# SCH5_Main_computer_USB2-0.net
KiCad netlist of a schematic drawn in Altium Designer
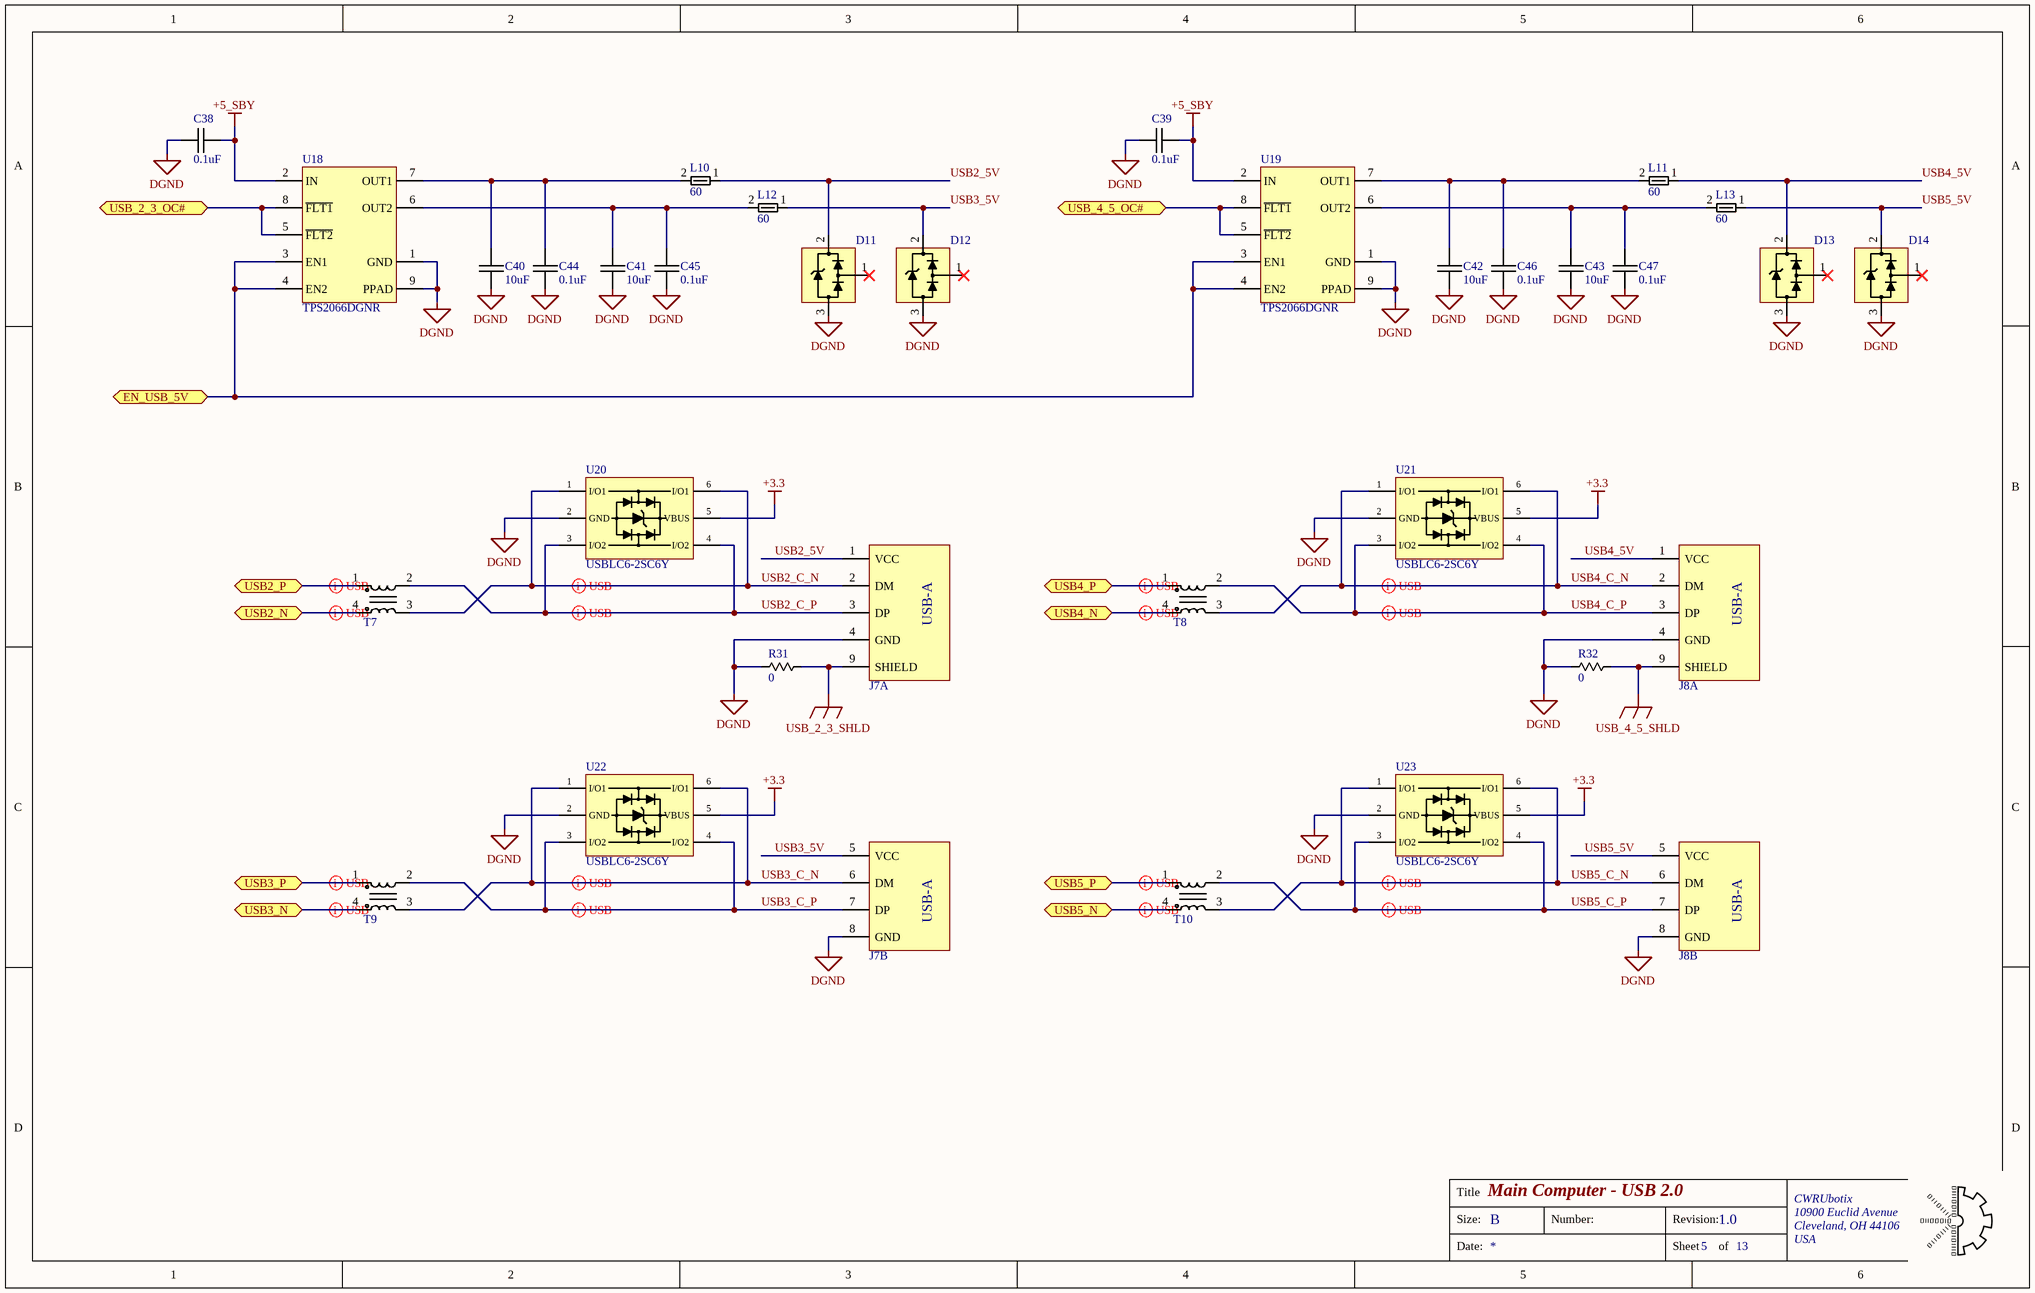
[diagram p0: SCH5_Main_computer_USB2-0.SchDoc]

(export (version "E")
  (design (tool "Eeschema 10.0.6"))
  (components
    (comp (ref "C38")
      (value "0.1uF")
      (footprint "chip_0603")
      (description "CAP, 0.1uF, ±10%, 16V, X7R, 0603")
      (fields (field (name "PART NUMBER") "CAP-00542") (field (name "TOLERANCE") "±10%"))
      (libsource (lib "Capacitors$") (part "CAP-00542"))
    )
    (comp (ref "C39")
      (value "0.1uF")
      (footprint "chip_0603")
      (description "CAP, 0.1uF, ±10%, 16V, X7R, 0603")
      (fields (field (name "PART NUMBER") "CAP-00542") (field (name "TOLERANCE") "±10%"))
      (libsource (lib "Capacitors$") (part "CAP-00542"))
    )
    (comp (ref "C40")
      (value "10uF")
      (footprint "chip_1206")
      (description "CAP, 10uF, ±10%, 25V, X7R, 1206")
      (fields (field (name "PART NUMBER") "CAP-00539") (field (name "TOLERANCE") "±10%"))
      (libsource (lib "Capacitors$") (part "CAP-00539"))
    )
    (comp (ref "C41")
      (value "10uF")
      (footprint "chip_1206")
      (description "CAP, 10uF, ±10%, 25V, X7R, 1206")
      (fields (field (name "PART NUMBER") "CAP-00539") (field (name "TOLERANCE") "±10%"))
      (libsource (lib "Capacitors$") (part "CAP-00539"))
    )
    (comp (ref "C42")
      (value "10uF")
      (footprint "chip_1206")
      (description "CAP, 10uF, ±10%, 25V, X7R, 1206")
      (fields (field (name "PART NUMBER") "CAP-00539") (field (name "TOLERANCE") "±10%"))
      (libsource (lib "Capacitors$") (part "CAP-00539"))
    )
    (comp (ref "C43")
      (value "10uF")
      (footprint "chip_1206")
      (description "CAP, 10uF, ±10%, 25V, X7R, 1206")
      (fields (field (name "PART NUMBER") "CAP-00539") (field (name "TOLERANCE") "±10%"))
      (libsource (lib "Capacitors$") (part "CAP-00539"))
    )
    (comp (ref "C44")
      (value "0.1uF")
      (footprint "chip_0603")
      (description "CAP, 0.1uF, ±10%, 16V, X7R, 0603")
      (fields (field (name "PART NUMBER") "CAP-00542") (field (name "TOLERANCE") "±10%"))
      (libsource (lib "Capacitors$") (part "CAP-00542"))
    )
    (comp (ref "C45")
      (value "0.1uF")
      (footprint "chip_0603")
      (description "CAP, 0.1uF, ±10%, 16V, X7R, 0603")
      (fields (field (name "PART NUMBER") "CAP-00542") (field (name "TOLERANCE") "±10%"))
      (libsource (lib "Capacitors$") (part "CAP-00542"))
    )
    (comp (ref "C46")
      (value "0.1uF")
      (footprint "chip_0603")
      (description "CAP, 0.1uF, ±10%, 16V, X7R, 0603")
      (fields (field (name "PART NUMBER") "CAP-00542") (field (name "TOLERANCE") "±10%"))
      (libsource (lib "Capacitors$") (part "CAP-00542"))
    )
    (comp (ref "C47")
      (value "0.1uF")
      (footprint "chip_0603")
      (description "CAP, 0.1uF, ±10%, 16V, X7R, 0603")
      (fields (field (name "PART NUMBER") "CAP-00542") (field (name "TOLERANCE") "±10%"))
      (libsource (lib "Capacitors$") (part "CAP-00542"))
    )
    (comp (ref "D11")
      (value "DLPT05")
      (footprint "sot-23-3")
      (description "TVS, Steering (Rail-Rail), 9.8V Clamping, 17A Peak Pulse, SOT-23")
      (fields (field (name "PART NUMBER") "DIO-00057") (field (name "MANUFACTURER") "Diodes Incorporated"))
      (libsource (lib "Diodes$") (part "DIO-00057"))
    )
    (comp (ref "D12")
      (value "DLPT05")
      (footprint "sot-23-3")
      (description "TVS, Steering (Rail-Rail), 9.8V Clamping, 17A Peak Pulse, SOT-23")
      (fields (field (name "PART NUMBER") "DIO-00057") (field (name "MANUFACTURER") "Diodes Incorporated"))
      (libsource (lib "Diodes$") (part "DIO-00057"))
    )
    (comp (ref "D13")
      (value "DLPT05")
      (footprint "sot-23-3")
      (description "TVS, Steering (Rail-Rail), 9.8V Clamping, 17A Peak Pulse, SOT-23")
      (fields (field (name "PART NUMBER") "DIO-00057") (field (name "MANUFACTURER") "Diodes Incorporated"))
      (libsource (lib "Diodes$") (part "DIO-00057"))
    )
    (comp (ref "D14")
      (value "DLPT05")
      (footprint "sot-23-3")
      (description "TVS, Steering (Rail-Rail), 9.8V Clamping, 17A Peak Pulse, SOT-23")
      (fields (field (name "PART NUMBER") "DIO-00057") (field (name "MANUFACTURER") "Diodes Incorporated"))
      (libsource (lib "Diodes$") (part "DIO-00057"))
    )
    (comp (ref "J7")
      (value "usb_a_x2")
      (footprint "CUI_UJ2-ADH-1-TH")
      (description "USB-A Jack x2, USB 2.0, Right-Angle, Thru-Hole")
      (fields (field (name "PART NUMBER") "CONN-00068") (field (name "MANUFACTURER") "CUI"))
      (libsource (lib "Connectors$") (part "CONN-00068"))
    )
    (comp (ref "J8")
      (value "usb_a_x2")
      (footprint "CUI_UJ2-ADH-1-TH")
      (description "USB-A Jack x2, USB 2.0, Right-Angle, Thru-Hole")
      (fields (field (name "PART NUMBER") "CONN-00068") (field (name "MANUFACTURER") "CUI"))
      (libsource (lib "Connectors$") (part "CONN-00068"))
    )
    (comp (ref "L10")
      (value "bead_0")
      (footprint "CHIP_0805_FE")
      (description "Fe Bead, 60 @ 100MH, 3A, 0805")
      (fields
        (field (name "PART NUMBER") "MAG-00125")
        (field (name "IMPEDANCE") "60")
        (field (name "MANUFACTURER") "Pulse Electronics")
      )
      (libsource (lib "Magnetics$") (part "MAG-00125"))
    )
    (comp (ref "L11")
      (value "bead_0")
      (footprint "CHIP_0805_FE")
      (description "Fe Bead, 60 @ 100MH, 3A, 0805")
      (fields
        (field (name "PART NUMBER") "MAG-00125")
        (field (name "IMPEDANCE") "60")
        (field (name "MANUFACTURER") "Pulse Electronics")
      )
      (libsource (lib "Magnetics$") (part "MAG-00125"))
    )
    (comp (ref "L12")
      (value "bead_0")
      (footprint "CHIP_0805_FE")
      (description "Fe Bead, 60 @ 100MH, 3A, 0805")
      (fields
        (field (name "PART NUMBER") "MAG-00125")
        (field (name "IMPEDANCE") "60")
        (field (name "MANUFACTURER") "Pulse Electronics")
      )
      (libsource (lib "Magnetics$") (part "MAG-00125"))
    )
    (comp (ref "L13")
      (value "bead_0")
      (footprint "CHIP_0805_FE")
      (description "Fe Bead, 60 @ 100MH, 3A, 0805")
      (fields
        (field (name "PART NUMBER") "MAG-00125")
        (field (name "IMPEDANCE") "60")
        (field (name "MANUFACTURER") "Pulse Electronics")
      )
      (libsource (lib "Magnetics$") (part "MAG-00125"))
    )
    (comp (ref "R31")
      (value "0")
      (footprint "chip_0805")
      (description "RES SMD 0 OHM 1/8W 0805 Thick Film")
      (fields (field (name "PART NUMBER") "RES-00720") (field (name "TOLERANCE") "Jumper"))
      (libsource (lib "Resistors$") (part "RES-00720"))
    )
    (comp (ref "R32")
      (value "0")
      (footprint "chip_0805")
      (description "RES SMD 0 OHM 1/8W 0805 Thick Film")
      (fields (field (name "PART NUMBER") "RES-00720") (field (name "TOLERANCE") "Jumper"))
      (libsource (lib "Resistors$") (part "RES-00720"))
    )
    (comp (ref "T7")
      (value "DLW21HN900SQ2L")
      (footprint "MURATA_DLW21H")
      (description "CMC, 330mA 2-CH 90 OHM @ 100MHz SMD")
      (fields (field (name "PART NUMBER") "MAG-00121") (field (name "MANUFACTURER") "Murata"))
      (libsource (lib "Magnetics$") (part "MAG-00121"))
    )
    (comp (ref "T8")
      (value "DLW21HN900SQ2L")
      (footprint "MURATA_DLW21H")
      (description "CMC, 330mA 2-CH 90 OHM @ 100MHz SMD")
      (fields (field (name "PART NUMBER") "MAG-00121") (field (name "MANUFACTURER") "Murata"))
      (libsource (lib "Magnetics$") (part "MAG-00121"))
    )
    (comp (ref "T9")
      (value "DLW21HN900SQ2L")
      (footprint "MURATA_DLW21H")
      (description "CMC, 330mA 2-CH 90 OHM @ 100MHz SMD")
      (fields (field (name "PART NUMBER") "MAG-00121") (field (name "MANUFACTURER") "Murata"))
      (libsource (lib "Magnetics$") (part "MAG-00121"))
    )
    (comp (ref "T10")
      (value "DLW21HN900SQ2L")
      (footprint "MURATA_DLW21H")
      (description "CMC, 330mA 2-CH 90 OHM @ 100MHz SMD")
      (fields (field (name "PART NUMBER") "MAG-00121") (field (name "MANUFACTURER") "Murata"))
      (libsource (lib "Magnetics$") (part "MAG-00121"))
    )
    (comp (ref "U18")
      (value "TPS2066DGNR")
      (footprint "VSSOP-8-PPAD")
      (description "IC, Power Switch 1:2, 8-MSOP")
      (fields (field (name "PART NUMBER") "PWREG-00052") (field (name "MANUFACTURER") "TI"))
      (libsource (lib "Power Reg$") (part "PWREG-00052"))
    )
    (comp (ref "U19")
      (value "TPS2066DGNR")
      (footprint "VSSOP-8-PPAD")
      (description "IC, Power Switch 1:2, 8-MSOP")
      (fields (field (name "PART NUMBER") "PWREG-00052") (field (name "MANUFACTURER") "TI"))
      (libsource (lib "Power Reg$") (part "PWREG-00052"))
    )
    (comp (ref "U20")
      (value "USBLC6-2SC6Y")
      (footprint "sot-23-6")
      (description "ESD Protec, 2-Ch, 2.5pF, 17V clamping voltage, SOT23-6")
      (fields (field (name "PART NUMBER") "DIO-00069") (field (name "MANUFACTURER") "ST"))
      (libsource (lib "Diodes$") (part "DIO-00069"))
    )
    (comp (ref "U21")
      (value "USBLC6-2SC6Y")
      (footprint "sot-23-6")
      (description "ESD Protec, 2-Ch, 2.5pF, 17V clamping voltage, SOT23-6")
      (fields (field (name "PART NUMBER") "DIO-00069") (field (name "MANUFACTURER") "ST"))
      (libsource (lib "Diodes$") (part "DIO-00069"))
    )
    (comp (ref "U22")
      (value "USBLC6-2SC6Y")
      (footprint "sot-23-6")
      (description "ESD Protec, 2-Ch, 2.5pF, 17V clamping voltage, SOT23-6")
      (fields (field (name "PART NUMBER") "DIO-00069") (field (name "MANUFACTURER") "ST"))
      (libsource (lib "Diodes$") (part "DIO-00069"))
    )
    (comp (ref "U23")
      (value "USBLC6-2SC6Y")
      (footprint "sot-23-6")
      (description "ESD Protec, 2-Ch, 2.5pF, 17V clamping voltage, SOT23-6")
      (fields (field (name "PART NUMBER") "DIO-00069") (field (name "MANUFACTURER") "ST"))
      (libsource (lib "Diodes$") (part "DIO-00069"))
    )
  )
  (nets
    (net (code "1") (name "+3.3") (class "Default")
      (node (ref "U20") (pin "5") (pinfunction "VBUS_5") (pintype "passive"))
      (node (ref "U21") (pin "5") (pinfunction "VBUS_5") (pintype "passive"))
      (node (ref "U22") (pin "5") (pinfunction "VBUS_5") (pintype "passive"))
      (node (ref "U23") (pin "5") (pinfunction "VBUS_5") (pintype "passive"))
    )
    (net (code "2") (name "+5_SBY") (class "Default")
      (node (ref "C38") (pin "2") (pinfunction "2_2") (pintype "passive"))
      (node (ref "C39") (pin "2") (pinfunction "2_2") (pintype "passive"))
      (node (ref "U18") (pin "2") (pinfunction "IN_2") (pintype "passive"))
      (node (ref "U19") (pin "2") (pinfunction "IN_2") (pintype "passive"))
    )
    (net (code "3") (name "/EN_USB_5V") (class "Default")
      (node (ref "U18") (pin "3") (pinfunction "EN1_3") (pintype "passive"))
      (node (ref "U18") (pin "4") (pinfunction "EN2_4") (pintype "passive"))
      (node (ref "U19") (pin "3") (pinfunction "EN1_3") (pintype "passive"))
      (node (ref "U19") (pin "4") (pinfunction "EN2_4") (pintype "passive"))
    )
    (net (code "4") (name "/USB2_5V") (class "Default")
      (node (ref "D11") (pin "2") (pinfunction "VCC_2") (pintype "passive"))
      (node (ref "J7") (pin "1") (pinfunction "VCC_1") (pintype "passive"))
      (node (ref "L10") (pin "1") (pinfunction "1_1") (pintype "passive"))
    )
    (net (code "5") (name "/USB2_C_N") (class "Default")
      (node (ref "J7") (pin "2") (pinfunction "DM_2") (pintype "passive"))
      (node (ref "T7") (pin "3") (pinfunction "3_3") (pintype "passive"))
      (node (ref "U20") (pin "1") (pinfunction "I/O1_1") (pintype "passive"))
      (node (ref "U20") (pin "6") (pinfunction "I/O1_6") (pintype "passive"))
    )
    (net (code "6") (name "/USB2_C_P") (class "Default")
      (node (ref "J7") (pin "3") (pinfunction "DP_3") (pintype "passive"))
      (node (ref "T7") (pin "2") (pinfunction "2_2") (pintype "passive"))
      (node (ref "U20") (pin "3") (pinfunction "I/O2_3") (pintype "passive"))
      (node (ref "U20") (pin "4") (pinfunction "I/O2_4") (pintype "passive"))
    )
    (net (code "7") (name "/USB2_N") (class "Default")
      (node (ref "T7") (pin "4") (pinfunction "34_4") (pintype "passive"))
    )
    (net (code "8") (name "/USB2_P") (class "Default")
      (node (ref "T7") (pin "1") (pinfunction "1_1") (pintype "passive"))
    )
    (net (code "9") (name "/USB3_5V") (class "Default")
      (node (ref "D12") (pin "2") (pinfunction "VCC_2") (pintype "passive"))
      (node (ref "J7") (pin "5") (pinfunction "VCC_5") (pintype "passive"))
      (node (ref "L12") (pin "1") (pinfunction "1_1") (pintype "passive"))
    )
    (net (code "10") (name "/USB3_C_N") (class "Default")
      (node (ref "J7") (pin "6") (pinfunction "DM_6") (pintype "passive"))
      (node (ref "T9") (pin "3") (pinfunction "3_3") (pintype "passive"))
      (node (ref "U22") (pin "1") (pinfunction "I/O1_1") (pintype "passive"))
      (node (ref "U22") (pin "6") (pinfunction "I/O1_6") (pintype "passive"))
    )
    (net (code "11") (name "/USB3_C_P") (class "Default")
      (node (ref "J7") (pin "7") (pinfunction "DP_7") (pintype "passive"))
      (node (ref "T9") (pin "2") (pinfunction "2_2") (pintype "passive"))
      (node (ref "U22") (pin "3") (pinfunction "I/O2_3") (pintype "passive"))
      (node (ref "U22") (pin "4") (pinfunction "I/O2_4") (pintype "passive"))
    )
    (net (code "12") (name "/USB3_N") (class "Default")
      (node (ref "T9") (pin "4") (pinfunction "34_4") (pintype "passive"))
    )
    (net (code "13") (name "/USB3_P") (class "Default")
      (node (ref "T9") (pin "1") (pinfunction "1_1") (pintype "passive"))
    )
    (net (code "14") (name "/USB4_5V") (class "Default")
      (node (ref "D13") (pin "2") (pinfunction "VCC_2") (pintype "passive"))
      (node (ref "J8") (pin "1") (pinfunction "VCC_1") (pintype "passive"))
      (node (ref "L11") (pin "1") (pinfunction "1_1") (pintype "passive"))
    )
    (net (code "15") (name "/USB4_C_N") (class "Default")
      (node (ref "J8") (pin "2") (pinfunction "DM_2") (pintype "passive"))
      (node (ref "T8") (pin "3") (pinfunction "3_3") (pintype "passive"))
      (node (ref "U21") (pin "1") (pinfunction "I/O1_1") (pintype "passive"))
      (node (ref "U21") (pin "6") (pinfunction "I/O1_6") (pintype "passive"))
    )
    (net (code "16") (name "/USB4_C_P") (class "Default")
      (node (ref "J8") (pin "3") (pinfunction "DP_3") (pintype "passive"))
      (node (ref "T8") (pin "2") (pinfunction "2_2") (pintype "passive"))
      (node (ref "U21") (pin "3") (pinfunction "I/O2_3") (pintype "passive"))
      (node (ref "U21") (pin "4") (pinfunction "I/O2_4") (pintype "passive"))
    )
    (net (code "17") (name "/USB4_N") (class "Default")
      (node (ref "T8") (pin "4") (pinfunction "34_4") (pintype "passive"))
    )
    (net (code "18") (name "/USB4_P") (class "Default")
      (node (ref "T8") (pin "1") (pinfunction "1_1") (pintype "passive"))
    )
    (net (code "19") (name "/USB5_5V") (class "Default")
      (node (ref "D14") (pin "2") (pinfunction "VCC_2") (pintype "passive"))
      (node (ref "J8") (pin "5") (pinfunction "VCC_5") (pintype "passive"))
      (node (ref "L13") (pin "1") (pinfunction "1_1") (pintype "passive"))
    )
    (net (code "20") (name "/USB5_C_N") (class "Default")
      (node (ref "J8") (pin "6") (pinfunction "DM_6") (pintype "passive"))
      (node (ref "T10") (pin "3") (pinfunction "3_3") (pintype "passive"))
      (node (ref "U23") (pin "1") (pinfunction "I/O1_1") (pintype "passive"))
      (node (ref "U23") (pin "6") (pinfunction "I/O1_6") (pintype "passive"))
    )
    (net (code "21") (name "/USB5_C_P") (class "Default")
      (node (ref "J8") (pin "7") (pinfunction "DP_7") (pintype "passive"))
      (node (ref "T10") (pin "2") (pinfunction "2_2") (pintype "passive"))
      (node (ref "U23") (pin "3") (pinfunction "I/O2_3") (pintype "passive"))
      (node (ref "U23") (pin "4") (pinfunction "I/O2_4") (pintype "passive"))
    )
    (net (code "22") (name "/USB5_N") (class "Default")
      (node (ref "T10") (pin "4") (pinfunction "34_4") (pintype "passive"))
    )
    (net (code "23") (name "/USB5_P") (class "Default")
      (node (ref "T10") (pin "1") (pinfunction "1_1") (pintype "passive"))
    )
    (net (code "24") (name "/USB_2_3_OC#") (class "Default")
      (node (ref "U18") (pin "5") (pinfunction "~{FLT2}_5") (pintype "passive"))
      (node (ref "U18") (pin "8") (pinfunction "~{FLT1}_8") (pintype "passive"))
    )
    (net (code "25") (name "/USB_4_5_OC#") (class "Default")
      (node (ref "U19") (pin "5") (pinfunction "~{FLT2}_5") (pintype "passive"))
      (node (ref "U19") (pin "8") (pinfunction "~{FLT1}_8") (pintype "passive"))
    )
    (net (code "26") (name "DGND") (class "Default")
      (node (ref "C38") (pin "1") (pinfunction "1_1") (pintype "passive"))
      (node (ref "C39") (pin "1") (pinfunction "1_1") (pintype "passive"))
      (node (ref "C40") (pin "2") (pinfunction "2_2") (pintype "passive"))
      (node (ref "C41") (pin "2") (pinfunction "2_2") (pintype "passive"))
      (node (ref "C42") (pin "2") (pinfunction "2_2") (pintype "passive"))
      (node (ref "C43") (pin "2") (pinfunction "2_2") (pintype "passive"))
      (node (ref "C44") (pin "1") (pinfunction "1_1") (pintype "passive"))
      (node (ref "C45") (pin "1") (pinfunction "1_1") (pintype "passive"))
      (node (ref "C46") (pin "1") (pinfunction "1_1") (pintype "passive"))
      (node (ref "C47") (pin "1") (pinfunction "1_1") (pintype "passive"))
      (node (ref "D11") (pin "3") (pinfunction "GND_3") (pintype "passive"))
      (node (ref "D12") (pin "3") (pinfunction "GND_3") (pintype "passive"))
      (node (ref "D13") (pin "3") (pinfunction "GND_3") (pintype "passive"))
      (node (ref "D14") (pin "3") (pinfunction "GND_3") (pintype "passive"))
      (node (ref "J7") (pin "4") (pinfunction "GND_4") (pintype "passive"))
      (node (ref "J7") (pin "8") (pinfunction "GND_8") (pintype "passive"))
      (node (ref "J8") (pin "4") (pinfunction "GND_4") (pintype "passive"))
      (node (ref "J8") (pin "8") (pinfunction "GND_8") (pintype "passive"))
      (node (ref "R31") (pin "1") (pinfunction "1_1") (pintype "passive"))
      (node (ref "R32") (pin "1") (pinfunction "1_1") (pintype "passive"))
      (node (ref "U18") (pin "1") (pinfunction "GND_1") (pintype "passive"))
      (node (ref "U18") (pin "9") (pinfunction "PPAD_9") (pintype "passive"))
      (node (ref "U19") (pin "1") (pinfunction "GND_1") (pintype "passive"))
      (node (ref "U19") (pin "9") (pinfunction "PPAD_9") (pintype "passive"))
      (node (ref "U20") (pin "2") (pinfunction "GND_2") (pintype "passive"))
      (node (ref "U21") (pin "2") (pinfunction "GND_2") (pintype "passive"))
      (node (ref "U22") (pin "2") (pinfunction "GND_2") (pintype "passive"))
      (node (ref "U23") (pin "2") (pinfunction "GND_2") (pintype "passive"))
    )
    (net (code "27") (name "Net-(U18-OUT1)") (class "Default")
      (node (ref "C40") (pin "1") (pinfunction "1_1") (pintype "passive"))
      (node (ref "C44") (pin "2") (pinfunction "2_2") (pintype "passive"))
      (node (ref "L10") (pin "2") (pinfunction "2_2") (pintype "passive"))
      (node (ref "U18") (pin "7") (pinfunction "OUT1_7") (pintype "passive"))
    )
    (net (code "28") (name "Net-(U18-OUT2)") (class "Default")
      (node (ref "C41") (pin "1") (pinfunction "1_1") (pintype "passive"))
      (node (ref "C45") (pin "2") (pinfunction "2_2") (pintype "passive"))
      (node (ref "L12") (pin "2") (pinfunction "2_2") (pintype "passive"))
      (node (ref "U18") (pin "6") (pinfunction "OUT2_6") (pintype "passive"))
    )
    (net (code "29") (name "Net-(U19-OUT1)") (class "Default")
      (node (ref "C42") (pin "1") (pinfunction "1_1") (pintype "passive"))
      (node (ref "C46") (pin "2") (pinfunction "2_2") (pintype "passive"))
      (node (ref "L11") (pin "2") (pinfunction "2_2") (pintype "passive"))
      (node (ref "U19") (pin "7") (pinfunction "OUT1_7") (pintype "passive"))
    )
    (net (code "30") (name "Net-(U19-OUT2)") (class "Default")
      (node (ref "C43") (pin "1") (pinfunction "1_1") (pintype "passive"))
      (node (ref "C47") (pin "2") (pinfunction "2_2") (pintype "passive"))
      (node (ref "L13") (pin "2") (pinfunction "2_2") (pintype "passive"))
      (node (ref "U19") (pin "6") (pinfunction "OUT2_6") (pintype "passive"))
    )
    (net (code "31") (name "USB_2_3_SHLD") (class "Default")
      (node (ref "J7") (pin "9") (pinfunction "SHIELD_9") (pintype "passive"))
      (node (ref "R31") (pin "2") (pinfunction "2_2") (pintype "passive"))
    )
    (net (code "32") (name "USB_4_5_SHLD") (class "Default")
      (node (ref "J8") (pin "9") (pinfunction "SHIELD_9") (pintype "passive"))
      (node (ref "R32") (pin "2") (pinfunction "2_2") (pintype "passive"))
    )
    (net (code "33") (name "unconnected-(D11-LINE-Pad1)") (class "Default")
      (node (ref "D11") (pin "1") (pinfunction "LINE_1") (pintype "passive+no_connect"))
    )
    (net (code "34") (name "unconnected-(D12-LINE-Pad1)") (class "Default")
      (node (ref "D12") (pin "1") (pinfunction "LINE_1") (pintype "passive+no_connect"))
    )
    (net (code "35") (name "unconnected-(D13-LINE-Pad1)") (class "Default")
      (node (ref "D13") (pin "1") (pinfunction "LINE_1") (pintype "passive+no_connect"))
    )
    (net (code "36") (name "unconnected-(D14-LINE-Pad1)") (class "Default")
      (node (ref "D14") (pin "1") (pinfunction "LINE_1") (pintype "passive+no_connect"))
    )
  )
)
